# Drone-Battery_Connection.net
KiCad netlist of a schematic drawn in EAGLE
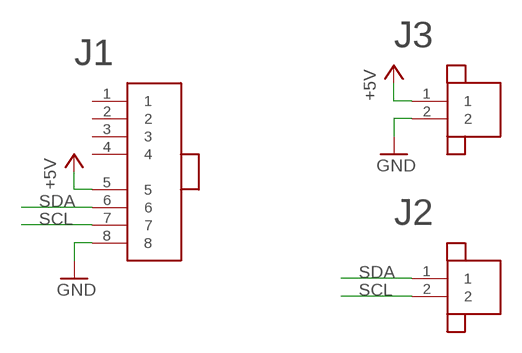
[diagram p0: schematic, sheet 1]

(export (version "E")
  (design (tool "Eeschema 10.0.6"))
  (components
    (comp (ref "J1")
      (value "SPRING_BTB_8POS_MALE")
      (footprint "eagle-import:SPRING_BTB_8POS_MALE")
      (libsource (lib "eagle-import") (part "SPRING_BTB_8POS_MALE"))
    )
    (comp (ref "J2")
      (value "JST_SH_2POS")
      (footprint "eagle-import:JST_SH_2POS")
      (libsource (lib "eagle-import") (part "JST_SH_2POS"))
    )
    (comp (ref "J3")
      (value "JST_SH_2POS")
      (footprint "eagle-import:JST_SH_2POS")
      (libsource (lib "eagle-import") (part "JST_SH_2POS"))
    )
  )
  (nets
    (net (code "1") (name "+5V") (class "Default")
      (node (ref "J1") (pin "5") (pinfunction "5_5") (pintype "bidirectional"))
      (node (ref "J3") (pin "1") (pinfunction "1_1") (pintype "bidirectional"))
    )
    (net (code "2") (name "/SCL") (class "Default")
      (node (ref "J1") (pin "7") (pinfunction "7_7") (pintype "bidirectional"))
      (node (ref "J2") (pin "2") (pinfunction "2_2") (pintype "bidirectional"))
    )
    (net (code "3") (name "/SDA") (class "Default")
      (node (ref "J1") (pin "6") (pinfunction "6_6") (pintype "bidirectional"))
      (node (ref "J2") (pin "1") (pinfunction "1_1") (pintype "bidirectional"))
    )
    (net (code "4") (name "GND") (class "Default")
      (node (ref "J1") (pin "8") (pinfunction "8_8") (pintype "bidirectional"))
      (node (ref "J3") (pin "2") (pinfunction "2_2") (pintype "bidirectional"))
    )
    (net (code "5") (name "unconnected-(J1-Pad1)") (class "Default")
      (node (ref "J1") (pin "1") (pinfunction "1_1") (pintype "bidirectional"))
    )
    (net (code "6") (name "unconnected-(J1-Pad2)") (class "Default")
      (node (ref "J1") (pin "2") (pinfunction "2_2") (pintype "bidirectional"))
    )
    (net (code "7") (name "unconnected-(J1-Pad3)") (class "Default")
      (node (ref "J1") (pin "3") (pinfunction "3_3") (pintype "bidirectional"))
    )
    (net (code "8") (name "unconnected-(J1-Pad4)") (class "Default")
      (node (ref "J1") (pin "4") (pinfunction "4_4") (pintype "bidirectional"))
    )
  )
)
